# main.net
KiCad netlist of a schematic drawn in Altium Designer
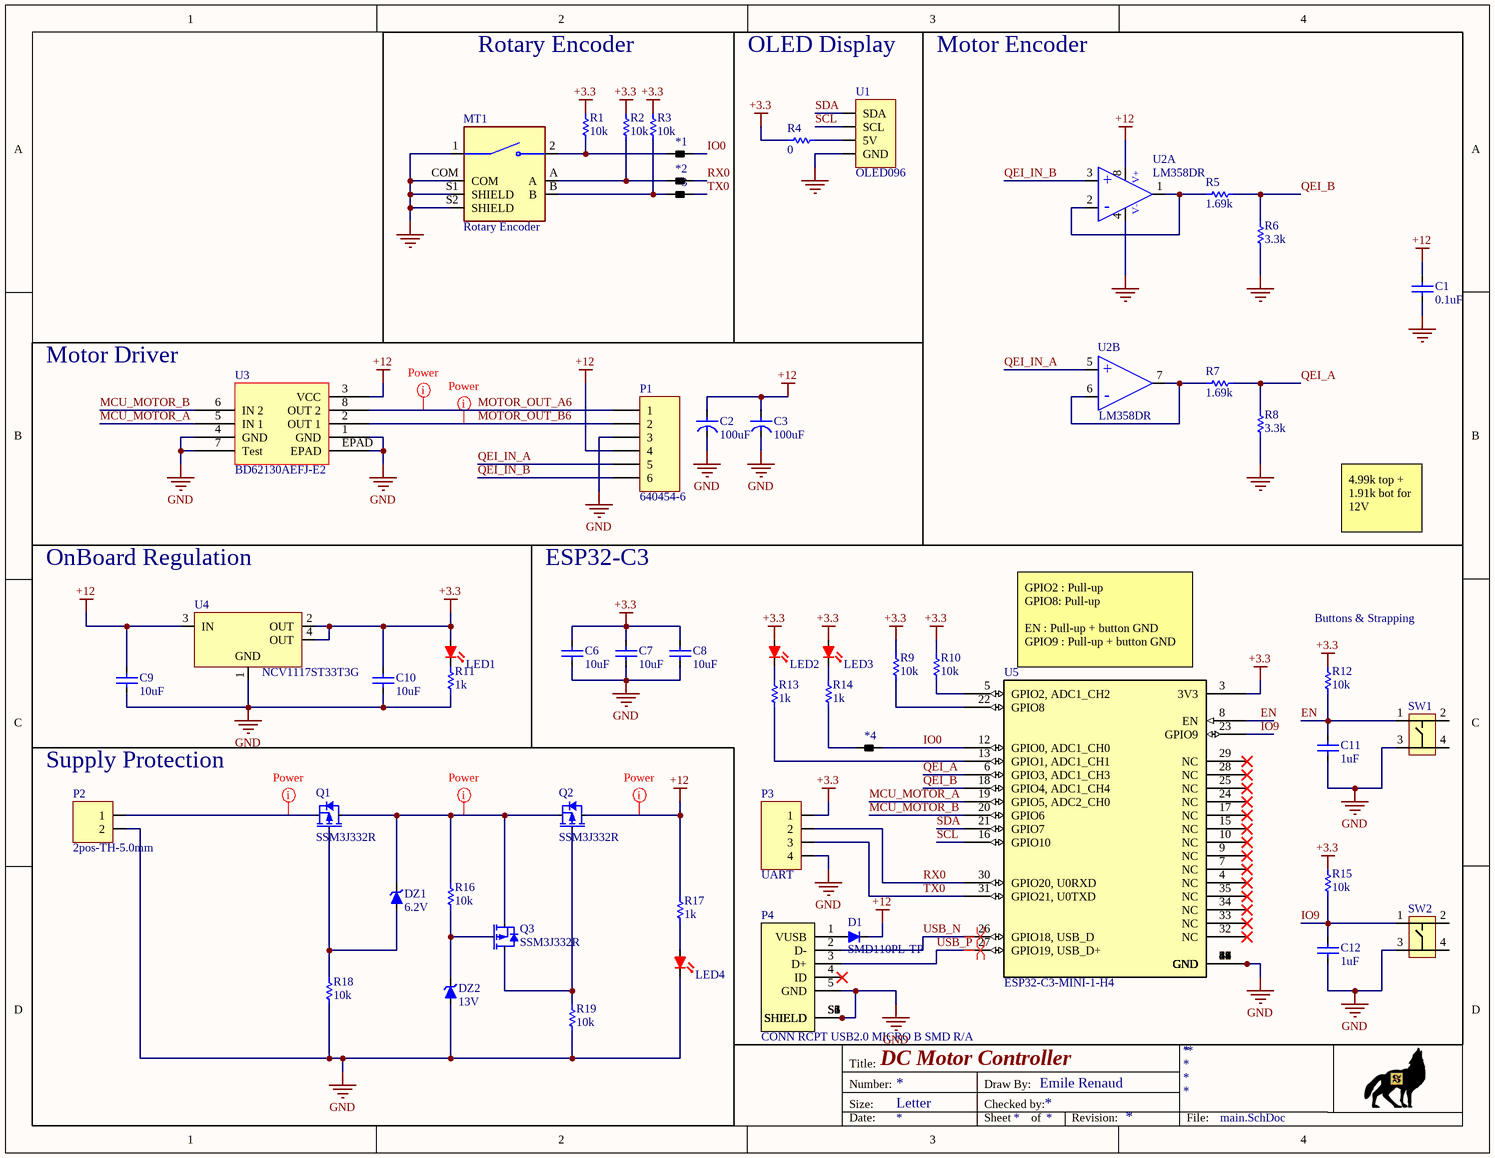
[diagram p0: main.SchDoc]

(export (version "E")
  (design (tool "Eeschema 10.0.6"))
  (components
    (comp (ref "*1")
      (value "NetTie_0603_Short")
      (footprint "NetTie-0603-short")
      (libsource (lib "JumpersAndHoles") (part "NetTie_0603_Short"))
    )
    (comp (ref "*2")
      (value "NetTie_0603_Short")
      (footprint "NetTie-0603-short")
      (libsource (lib "JumpersAndHoles") (part "NetTie_0603_Short"))
    )
    (comp (ref "*3")
      (value "NetTie_0603_Short")
      (footprint "NetTie-0603-short")
      (libsource (lib "JumpersAndHoles") (part "NetTie_0603_Short"))
    )
    (comp (ref "*4")
      (value "NetTie_0603_Short")
      (footprint "NetTie-0603-short")
      (libsource (lib "JumpersAndHoles") (part "NetTie_0603_Short"))
    )
    (comp (ref "C1")
      (value "0.1uF")
      (footprint "CAPACITOR-0603")
      (description "Capacitor-0603-0.1uF-50V-X7R")
      (libsource (lib "Capacitors") (part "Capacitor-0603-0.1uF-50V-X7R"))
    )
    (comp (ref "C2")
      (value "100uF")
      (footprint "CAPACITOR-Aluminium-5x11mm-2mmPitch")
      (description "CAP ALUM 100UF 20% 25V RADIAL")
      (libsource (lib "Capacitors-Electrolytic") (part "Capacitor-100uF-25V"))
    )
    (comp (ref "C3")
      (value "100uF")
      (footprint "CAPACITOR-Aluminium-5x11mm-2mmPitch")
      (description "CAP ALUM 100UF 20% 25V RADIAL")
      (libsource (lib "Capacitors-Electrolytic") (part "Capacitor-100uF-25V"))
    )
    (comp (ref "C6")
      (value "10uF")
      (footprint "CAPACITOR-0805")
      (description "Capacitor-0805-10uF-35V-X5R")
      (libsource (lib "Capacitors") (part "Capacitor-0805-10uF-35V-X5R"))
    )
    (comp (ref "C7")
      (value "10uF")
      (footprint "CAPACITOR-0805")
      (description "Capacitor-0805-10uF-35V-X5R")
      (libsource (lib "Capacitors") (part "Capacitor-0805-10uF-35V-X5R"))
    )
    (comp (ref "C8")
      (value "10uF")
      (footprint "CAPACITOR-0805")
      (description "Capacitor-0805-10uF-35V-X5R")
      (libsource (lib "Capacitors") (part "Capacitor-0805-10uF-35V-X5R"))
    )
    (comp (ref "C9")
      (value "10uF")
      (footprint "CAPACITOR-0805")
      (description "Capacitor-0805-10uF-35V-X5R")
      (libsource (lib "Capacitors") (part "Capacitor-0805-10uF-35V-X5R"))
    )
    (comp (ref "C10")
      (value "10uF")
      (footprint "CAPACITOR-0805")
      (description "Capacitor-0805-10uF-35V-X5R")
      (libsource (lib "Capacitors") (part "Capacitor-0805-10uF-35V-X5R"))
    )
    (comp (ref "C11")
      (value "1uF")
      (footprint "CAPACITOR-0603")
      (description "Capacitor-0603-1uF-25V-X5R")
      (libsource (lib "Capacitors") (part "Capacitor-0603-1uF-25V-X5R"))
    )
    (comp (ref "C12")
      (value "1uF")
      (footprint "CAPACITOR-0603")
      (description "Capacitor-0603-1uF-25V-X5R")
      (libsource (lib "Capacitors") (part "Capacitor-0603-1uF-25V-X5R"))
    )
    (comp (ref "D1")
      (value "SMD110PL-TP")
      (footprint "SOD-123F")
      (description "DIODE SCHOTTKY 100V 1A SOD123FL")
      (libsource (lib "diodes") (part "SMD110PL-TP"))
    )
    (comp (ref "DZ1")
      (value "BZT52C6V2-TP")
      (footprint "SOD-123")
      (description "Zener Diode 6.2 V 200 mW ±6% Surface Mount SOD-123")
      (fields (field (name "VOLT") "6.2V"))
      (libsource (lib "diodes-zener") (part "BZT52C6V2-TP"))
    )
    (comp (ref "DZ2")
      (value "BZT52C13-TP")
      (footprint "SOD-123")
      (description "Zener Diode 13 V 200 mW ±6% Surface Mount SOD-123")
      (fields (field (name "VOLT") "13V"))
      (libsource (lib "diodes-zener") (part "BZT52C13-TP"))
    )
    (comp (ref "LED1")
      (value "B1911USD-20D000114U1930")
      (footprint "LED-0603-2PIN")
      (description "LED RED CLEAR 1608 SMD")
      (libsource (lib "LEDs") (part "B1911USD-20D000114U1930"))
    )
    (comp (ref "LED2")
      (value "B1911USD-20D000114U1930")
      (footprint "LED-0603-2PIN")
      (description "LED RED CLEAR 1608 SMD")
      (libsource (lib "LEDs") (part "B1911USD-20D000114U1930"))
    )
    (comp (ref "LED3")
      (value "B1911USD-20D000114U1930")
      (footprint "LED-0603-2PIN")
      (description "LED RED CLEAR 1608 SMD")
      (libsource (lib "LEDs") (part "B1911USD-20D000114U1930"))
    )
    (comp (ref "LED4")
      (value "B1911USD-20D000114U1930")
      (footprint "LED-0603-2PIN")
      (description "LED RED CLEAR 1608 SMD")
      (libsource (lib "LEDs") (part "B1911USD-20D000114U1930"))
    )
    (comp (ref "MT1")
      (value "Rotary Encoder")
      (footprint "PCB_Footprints:XDCR_PEC11R-4215F-S0024")
      (description "Incremental Encoder, 12 Mm, Contact Rating 10 Ma - 5 Vdc")
      (fields (field (name "MP") "PEC11R-4215F-S0024"))
      (libsource (lib "Encoder") (part "PEC11R-4215F-S0024"))
    )
    (comp (ref "P1")
      (value "640454-6")
      (footprint "640454-6")
      (description "CONN HEADER VERT 6POS .100 TIN")
      (fields (field (name "MANUFACTURER") "TE Connectivity AMP Connectors"))
      (libsource (lib "header") (part "640454-6"))
    )
    (comp (ref "P2")
      (value "2pos-TH-5.0mm")
      (footprint "Weco 2")
      (description "2pos-TH-5.0mm Screw Terminal")
      (libsource (lib "ScrewTerminal") (part "2pos-TH-5.0mm"))
    )
    (comp (ref "P3")
      (value "UART")
      (footprint "HDR1X4")
      (description "4pos TH 2.54mm Header")
      (libsource (lib "header") (part "4pos-TH-2.54mm"))
    )
    (comp (ref "P4")
      (value "CONN RCPT USB2.0 MICRO B SMD R/A")
      (footprint "FCI_10118193-0001LF")
      (description "USB - micro B USB 2.0 Receptacle Connector 5 Position Surface Mount, Right Angle; Through Hole")
      (libsource (lib "PC-connector") (part "USB-Micro"))
    )
    (comp (ref "Q1")
      (value "SSM3J332R")
      (footprint "SOT-23-3")
      (description "P-Channel 30 V 6A (Ta) 1W (Ta) Surface Mount SOT-23F")
      (libsource (lib "FET-P-Small") (part "SSM3J332R"))
    )
    (comp (ref "Q2")
      (value "SSM3J332R")
      (footprint "SOT-23-3")
      (description "P-Channel 30 V 6A (Ta) 1W (Ta) Surface Mount SOT-23F")
      (libsource (lib "FET-P-Small") (part "SSM3J332R"))
    )
    (comp (ref "Q3")
      (value "SSM3J332R")
      (footprint "SOT-23-3")
      (description "P-Channel 30 V 6A (Ta) 1W (Ta) Surface Mount SOT-23F")
      (libsource (lib "FET-P-Small") (part "SSM3J332R"))
    )
    (comp (ref "R1")
      (value "10k")
      (footprint "Resistor-0603")
      (description "Resistor0603-10k")
      (fields (field (name "Comment") "SMT resistor"))
      (libsource (lib "Resistors") (part "Resistor0603-10k"))
    )
    (comp (ref "R2")
      (value "10k")
      (footprint "Resistor-0603")
      (description "Resistor0603-10k")
      (fields (field (name "Comment") "SMT resistor"))
      (libsource (lib "Resistors") (part "Resistor0603-10k"))
    )
    (comp (ref "R3")
      (value "10k")
      (footprint "Resistor-0603")
      (description "Resistor0603-10k")
      (fields (field (name "Comment") "SMT resistor"))
      (libsource (lib "Resistors") (part "Resistor0603-10k"))
    )
    (comp (ref "R4")
      (value "0")
      (footprint "Resistor-0603")
      (description "Resistor0603-0.0")
      (fields (field (name "Comment") "SMT resistor"))
      (libsource (lib "Resistors") (part "Resistor0603-0.0"))
    )
    (comp (ref "R5")
      (value "1.69k")
      (footprint "Resistor-0603")
      (description "Resistor0603-1.69k")
      (fields (field (name "Comment") "SMT resistor"))
      (libsource (lib "Resistors") (part "Resistor0603-1.69k"))
    )
    (comp (ref "R6")
      (value "3.3k")
      (footprint "Resistor-0603")
      (description "Resistor0603-3.3k")
      (fields (field (name "Comment") "SMT resistor"))
      (libsource (lib "Resistors") (part "Resistor0603-3.3k"))
    )
    (comp (ref "R7")
      (value "1.69k")
      (footprint "Resistor-0603")
      (description "Resistor0603-1.69k")
      (fields (field (name "Comment") "SMT resistor"))
      (libsource (lib "Resistors") (part "Resistor0603-1.69k"))
    )
    (comp (ref "R8")
      (value "3.3k")
      (footprint "Resistor-0603")
      (description "Resistor0603-3.3k")
      (fields (field (name "Comment") "SMT resistor"))
      (libsource (lib "Resistors") (part "Resistor0603-3.3k"))
    )
    (comp (ref "R9")
      (value "10k")
      (footprint "Resistor-0603")
      (description "Resistor0603-10k")
      (fields (field (name "Comment") "SMT resistor"))
      (libsource (lib "Resistors") (part "Resistor0603-10k"))
    )
    (comp (ref "R10")
      (value "10k")
      (footprint "Resistor-0603")
      (description "Resistor0603-10k")
      (fields (field (name "Comment") "SMT resistor"))
      (libsource (lib "Resistors") (part "Resistor0603-10k"))
    )
    (comp (ref "R11")
      (value "1k")
      (footprint "Resistor-0603")
      (description "Resistor0603-1k")
      (fields (field (name "Comment") "SMT resistor"))
      (libsource (lib "Resistors") (part "Resistor0603-1k"))
    )
    (comp (ref "R12")
      (value "10k")
      (footprint "Resistor-0603")
      (description "Resistor0603-10k")
      (fields (field (name "Comment") "SMT resistor"))
      (libsource (lib "Resistors") (part "Resistor0603-10k"))
    )
    (comp (ref "R13")
      (value "1k")
      (footprint "Resistor-0603")
      (description "Resistor0603-1k")
      (fields (field (name "Comment") "SMT resistor"))
      (libsource (lib "Resistors") (part "Resistor0603-1k"))
    )
    (comp (ref "R14")
      (value "1k")
      (footprint "Resistor-0603")
      (description "Resistor0603-1k")
      (fields (field (name "Comment") "SMT resistor"))
      (libsource (lib "Resistors") (part "Resistor0603-1k"))
    )
    (comp (ref "R15")
      (value "10k")
      (footprint "Resistor-0603")
      (description "Resistor0603-10k")
      (fields (field (name "Comment") "SMT resistor"))
      (libsource (lib "Resistors") (part "Resistor0603-10k"))
    )
    (comp (ref "R16")
      (value "10k")
      (footprint "Resistor-0603")
      (description "Resistor0603-10k")
      (fields (field (name "Comment") "SMT resistor"))
      (libsource (lib "Resistors") (part "Resistor0603-10k"))
    )
    (comp (ref "R17")
      (value "1k")
      (footprint "Resistor-0603")
      (description "Resistor0603-1k")
      (fields (field (name "Comment") "SMT resistor"))
      (libsource (lib "Resistors") (part "Resistor0603-1k"))
    )
    (comp (ref "R18")
      (value "10k")
      (footprint "Resistor-0603")
      (description "Resistor0603-10k")
      (fields (field (name "Comment") "SMT resistor"))
      (libsource (lib "Resistors") (part "Resistor0603-10k"))
    )
    (comp (ref "R19")
      (value "10k")
      (footprint "Resistor-0603")
      (description "Resistor0603-10k")
      (fields (field (name "Comment") "SMT resistor"))
      (libsource (lib "Resistors") (part "Resistor0603-10k"))
    )
    (comp (ref "SW1")
      (value "PTS815 SJM 250 SMTR LFS")
      (footprint "SW4_PTS815 SJM 250 SMTR LFS_CNK")
      (description "TACT 4.2 X 3.2, 2.5 MM H, 180GF,")
      (libsource (lib "THTPushButtonSwitches") (part "PTS815 SJM 250 SMTR LFS"))
    )
    (comp (ref "SW2")
      (value "PTS815 SJM 250 SMTR LFS")
      (footprint "SW4_PTS815 SJM 250 SMTR LFS_CNK")
      (description "TACT 4.2 X 3.2, 2.5 MM H, 180GF,")
      (libsource (lib "THTPushButtonSwitches") (part "PTS815 SJM 250 SMTR LFS"))
    )
    (comp (ref "U1")
      (value "OLED096")
      (footprint "OLED096")
      (description "OLED Display I2C 0.96in")
      (libsource (lib "LCD") (part "OLED096"))
    )
    (comp (ref "U2")
      (value "LM358DR")
      (footprint "SOIC-8")
      (description "IC OPAMP GP 2 CIRCUIT 8SOIC")
      (libsource (lib "OperationalAmplifiers") (part "LM358DR"))
    )
    (comp (ref "U3")
      (value "BD62130AEFJ-E2")
      (footprint "P-HSOP8")
      (description "1 CHANNEL H BRIDGE Motor. 28V, 3A")
      (libsource (lib "MotorDrivers") (part "BD62130AEFJ-E2"))
    )
    (comp (ref "U4")
      (value "NCV1117ST33T3G")
      (footprint "SOT-223-3/TO-261-3S")
      (description "IC REG LINEAR 3.3V 1A SOT223")
      (libsource (lib "PMIC-VoltageRegulators-LinearRegulators") (part "NCV1117ST33T3G"))
    )
    (comp (ref "U5")
      (value "ESP32-C3-MINI-1-H4")
      (footprint "ESP32-C3-MINI-1_EXP")
      (fields
        (field (name "MANUFACTURER_PART_NUMBER") "ESP32-C3-MINI-1-N4")
        (field (name "COPYRIGHT") "Copyright (C) 2023 Ultra Librarian. All rights reserved.")
      )
      (libsource (lib "Microcontrollers") (part "ESP32-C3-MINI-1-N4"))
    )
  )
  (nets
    (net (code "1") (name "+3.3") (class "Default")
      (node (ref "C10") (pin "2") (pinfunction "2_2") (pintype "passive"))
      (node (ref "C6") (pin "2") (pinfunction "2_2") (pintype "passive"))
      (node (ref "C7") (pin "2") (pinfunction "2_2") (pintype "passive"))
      (node (ref "C8") (pin "2") (pinfunction "2_2") (pintype "passive"))
      (node (ref "LED1") (pin "2") (pinfunction "R_2") (pintype "passive"))
      (node (ref "LED2") (pin "2") (pinfunction "R_2") (pintype "passive"))
      (node (ref "LED3") (pin "2") (pinfunction "R_2") (pintype "passive"))
      (node (ref "P3") (pin "1") (pinfunction "1_1") (pintype "passive"))
      (node (ref "R1") (pin "1") (pinfunction "1_1") (pintype "passive"))
      (node (ref "R10") (pin "1") (pinfunction "1_1") (pintype "passive"))
      (node (ref "R12") (pin "2") (pinfunction "2_2") (pintype "passive"))
      (node (ref "R15") (pin "2") (pinfunction "2_2") (pintype "passive"))
      (node (ref "R2") (pin "1") (pinfunction "1_1") (pintype "passive"))
      (node (ref "R3") (pin "1") (pinfunction "1_1") (pintype "passive"))
      (node (ref "R4") (pin "1") (pinfunction "1_1") (pintype "passive"))
      (node (ref "R9") (pin "1") (pinfunction "1_1") (pintype "passive"))
      (node (ref "U4") (pin "2") (pinfunction "OUT_2") (pintype "passive"))
      (node (ref "U4") (pin "4") (pinfunction "OUT_4") (pintype "passive"))
      (node (ref "U5") (pin "3") (pinfunction "3V3_3") (pintype "power_in"))
    )
    (net (code "2") (name "+12") (class "Default")
      (node (ref "C1") (pin "2") (pinfunction "2_2") (pintype "passive"))
      (node (ref "C2") (pin "1") (pinfunction "1_1") (pintype "passive"))
      (node (ref "C3") (pin "1") (pinfunction "1_1") (pintype "passive"))
      (node (ref "C9") (pin "2") (pinfunction "2_2") (pintype "passive"))
      (node (ref "D1") (pin "2") (pinfunction "K_2") (pintype "passive"))
      (node (ref "P1") (pin "4") (pinfunction "4_4") (pintype "passive"))
      (node (ref "Q2") (pin "3") (pinfunction "D_3") (pintype "passive"))
      (node (ref "R17") (pin "2") (pinfunction "2_2") (pintype "passive"))
      (node (ref "U2") (pin "8") (pinfunction "VS+_8") (pintype "passive"))
      (node (ref "U3") (pin "3") (pinfunction "VCC_3") (pintype "passive"))
      (node (ref "U4") (pin "3") (pinfunction "IN_3") (pintype "passive"))
    )
    (net (code "3") (name "/EN") (class "Default")
      (node (ref "C11") (pin "2") (pinfunction "2_2") (pintype "passive"))
      (node (ref "R12") (pin "1") (pinfunction "1_1") (pintype "passive"))
      (node (ref "SW1") (pin "1") (pinfunction "1_1") (pintype "passive"))
      (node (ref "U5") (pin "8") (pinfunction "EN_8") (pintype "input"))
    )
    (net (code "4") (name "/IO0") (class "Default")
      (node (ref "*1") (pin "1") (pinfunction "1_1") (pintype "passive"))
      (node (ref "*4") (pin "1") (pinfunction "1_1") (pintype "passive"))
      (node (ref "U5") (pin "12") (pinfunction "GPIO0,_ADC1_CH0_12") (pintype "bidirectional"))
    )
    (net (code "5") (name "/IO9") (class "Default")
      (node (ref "C12") (pin "2") (pinfunction "2_2") (pintype "passive"))
      (node (ref "R15") (pin "1") (pinfunction "1_1") (pintype "passive"))
      (node (ref "SW2") (pin "1") (pinfunction "1_1") (pintype "passive"))
      (node (ref "U5") (pin "23") (pinfunction "GPIO9_23") (pintype "bidirectional"))
    )
    (net (code "6") (name "/MCU_MOTOR_A") (class "Default")
      (node (ref "U3") (pin "5") (pinfunction "IN_1_5") (pintype "passive"))
      (node (ref "U5") (pin "19") (pinfunction "GPIO5,_ADC2_CH0_19") (pintype "bidirectional"))
    )
    (net (code "7") (name "/MCU_MOTOR_B") (class "Default")
      (node (ref "U3") (pin "6") (pinfunction "IN_2_6") (pintype "passive"))
      (node (ref "U5") (pin "20") (pinfunction "GPIO6_20") (pintype "bidirectional"))
    )
    (net (code "8") (name "/MOTOR_OUT_A6") (class "Default")
      (node (ref "P1") (pin "1") (pinfunction "1_1") (pintype "passive"))
      (node (ref "U3") (pin "8") (pinfunction "OUT_2_8") (pintype "passive"))
    )
    (net (code "9") (name "/MOTOR_OUT_B6") (class "Default")
      (node (ref "P1") (pin "2") (pinfunction "2_2") (pintype "passive"))
      (node (ref "U3") (pin "2") (pinfunction "OUT_1_2") (pintype "passive"))
    )
    (net (code "10") (name "/QEI_A") (class "Default")
      (node (ref "R7") (pin "2") (pinfunction "2_2") (pintype "passive"))
      (node (ref "R8") (pin "2") (pinfunction "2_2") (pintype "passive"))
      (node (ref "U5") (pin "6") (pinfunction "GPIO3,_ADC1_CH3_6") (pintype "bidirectional"))
    )
    (net (code "11") (name "/QEI_B") (class "Default")
      (node (ref "R5") (pin "2") (pinfunction "2_2") (pintype "passive"))
      (node (ref "R6") (pin "2") (pinfunction "2_2") (pintype "passive"))
      (node (ref "U5") (pin "18") (pinfunction "GPIO4,_ADC1_CH4_18") (pintype "bidirectional"))
    )
    (net (code "12") (name "/QEI_IN_A") (class "Default")
      (node (ref "P1") (pin "5") (pinfunction "5_5") (pintype "passive"))
      (node (ref "U2") (pin "5") (pinfunction "IN2+_5") (pintype "passive"))
    )
    (net (code "13") (name "/QEI_IN_B") (class "Default")
      (node (ref "P1") (pin "6") (pinfunction "6_6") (pintype "passive"))
      (node (ref "U2") (pin "3") (pinfunction "IN1+_3") (pintype "passive"))
    )
    (net (code "14") (name "/RX0") (class "Default")
      (node (ref "*2") (pin "1") (pinfunction "1_1") (pintype "passive"))
      (node (ref "P3") (pin "2") (pinfunction "2_2") (pintype "passive"))
      (node (ref "U5") (pin "30") (pinfunction "GPIO20,_U0RXD_30") (pintype "bidirectional"))
    )
    (net (code "15") (name "/SCL") (class "Default")
      (node (ref "U1") (pin "3") (pinfunction "SCL_3") (pintype "passive"))
      (node (ref "U5") (pin "16") (pinfunction "GPIO10_16") (pintype "bidirectional"))
    )
    (net (code "16") (name "/SDA") (class "Default")
      (node (ref "U1") (pin "4") (pinfunction "SDA_4") (pintype "passive"))
      (node (ref "U5") (pin "21") (pinfunction "GPIO7_21") (pintype "bidirectional"))
    )
    (net (code "17") (name "/TX0") (class "Default")
      (node (ref "*3") (pin "1") (pinfunction "1_1") (pintype "passive"))
      (node (ref "P3") (pin "3") (pinfunction "3_3") (pintype "passive"))
      (node (ref "U5") (pin "31") (pinfunction "GPIO21,_U0TXD_31") (pintype "bidirectional"))
    )
    (net (code "18") (name "/USB_N") (class "Default")
      (node (ref "P4") (pin "2") (pinfunction "D-_2") (pintype "passive"))
      (node (ref "U5") (pin "26") (pinfunction "GPIO18,_USB_D_26") (pintype "bidirectional"))
    )
    (net (code "19") (name "/USB_P") (class "Default")
      (node (ref "P4") (pin "3") (pinfunction "D+_3") (pintype "passive"))
      (node (ref "U5") (pin "27") (pinfunction "GPIO19,_USB_D+_27") (pintype "bidirectional"))
    )
    (net (code "20") (name "GND") (class "Default")
      (node (ref "C1") (pin "1") (pinfunction "1_1") (pintype "passive"))
      (node (ref "C10") (pin "1") (pinfunction "1_1") (pintype "passive"))
      (node (ref "C11") (pin "1") (pinfunction "1_1") (pintype "passive"))
      (node (ref "C12") (pin "1") (pinfunction "1_1") (pintype "passive"))
      (node (ref "C2") (pin "2") (pinfunction "2_2") (pintype "passive"))
      (node (ref "C3") (pin "2") (pinfunction "2_2") (pintype "passive"))
      (node (ref "C6") (pin "1") (pinfunction "1_1") (pintype "passive"))
      (node (ref "C7") (pin "1") (pinfunction "1_1") (pintype "passive"))
      (node (ref "C8") (pin "1") (pinfunction "1_1") (pintype "passive"))
      (node (ref "C9") (pin "1") (pinfunction "1_1") (pintype "passive"))
      (node (ref "DZ2") (pin "1") (pinfunction "A_1") (pintype "passive"))
      (node (ref "LED4") (pin "1") (pinfunction "K_1") (pintype "passive"))
      (node (ref "MT1") (pin "1") (pinfunction "1_1") (pintype "passive"))
      (node (ref "MT1") (pin "COM") (pinfunction "COM_COM") (pintype "passive"))
      (node (ref "MT1") (pin "S1") (pinfunction "SHIELD_S1") (pintype "passive"))
      (node (ref "MT1") (pin "S2") (pinfunction "SHIELD_S2") (pintype "passive"))
      (node (ref "P1") (pin "3") (pinfunction "3_3") (pintype "passive"))
      (node (ref "P2") (pin "2") (pinfunction "2_2") (pintype "passive"))
      (node (ref "P3") (pin "4") (pinfunction "4_4") (pintype "passive"))
      (node (ref "P4") (pin "5") (pinfunction "GND_5") (pintype "passive"))
      (node (ref "P4") (pin "S1") (pinfunction "SHIELD_S1") (pintype "passive"))
      (node (ref "P4") (pin "S2") (pinfunction "SHIELD_S2") (pintype "passive"))
      (node (ref "P4") (pin "S3") (pinfunction "SHIELD_S3") (pintype "passive"))
      (node (ref "P4") (pin "S4") (pinfunction "SHIELD_S4") (pintype "passive"))
      (node (ref "P4") (pin "S5") (pinfunction "SHIELD_S5") (pintype "passive"))
      (node (ref "P4") (pin "S6") (pinfunction "SHIELD_S6") (pintype "passive"))
      (node (ref "R11") (pin "1") (pinfunction "1_1") (pintype "passive"))
      (node (ref "R18") (pin "1") (pinfunction "1_1") (pintype "passive"))
      (node (ref "R19") (pin "1") (pinfunction "1_1") (pintype "passive"))
      (node (ref "R6") (pin "1") (pinfunction "1_1") (pintype "passive"))
      (node (ref "R8") (pin "1") (pinfunction "1_1") (pintype "passive"))
      (node (ref "SW1") (pin "3") (pinfunction "3_3") (pintype "passive"))
      (node (ref "SW2") (pin "3") (pinfunction "3_3") (pintype "passive"))
      (node (ref "U1") (pin "1") (pinfunction "GND_1") (pintype "passive"))
      (node (ref "U2") (pin "4") (pinfunction "VS-_4") (pintype "passive"))
      (node (ref "U3") (pin "1") (pinfunction "GND_1") (pintype "passive"))
      (node (ref "U3") (pin "4") (pinfunction "GND_4") (pintype "passive"))
      (node (ref "U3") (pin "7") (pinfunction "Test_7") (pintype "passive"))
      (node (ref "U3") (pin "EPAD") (pinfunction "EPAD_EPAD") (pintype "passive"))
      (node (ref "U4") (pin "1") (pinfunction "GND_1") (pintype "passive"))
      (node (ref "U5") (pin "1") (pinfunction "GND_1") (pintype "passive"))
      (node (ref "U5") (pin "11") (pinfunction "GND_11") (pintype "passive"))
      (node (ref "U5") (pin "14") (pinfunction "GND_14") (pintype "passive"))
      (node (ref "U5") (pin "2") (pinfunction "GND_2") (pintype "passive"))
      (node (ref "U5") (pin "36") (pinfunction "GND_36") (pintype "passive"))
      (node (ref "U5") (pin "37") (pinfunction "GND_37") (pintype "passive"))
      (node (ref "U5") (pin "38") (pinfunction "GND_38") (pintype "passive"))
      (node (ref "U5") (pin "39") (pinfunction "GND_39") (pintype "passive"))
      (node (ref "U5") (pin "40") (pinfunction "GND_40") (pintype "passive"))
      (node (ref "U5") (pin "41") (pinfunction "GND_41") (pintype "passive"))
      (node (ref "U5") (pin "42") (pinfunction "GND_42") (pintype "passive"))
      (node (ref "U5") (pin "43") (pinfunction "GND_43") (pintype "passive"))
      (node (ref "U5") (pin "44") (pinfunction "GND_44") (pintype "passive"))
      (node (ref "U5") (pin "45") (pinfunction "GND_45") (pintype "passive"))
      (node (ref "U5") (pin "46") (pinfunction "GND_46") (pintype "passive"))
      (node (ref "U5") (pin "47") (pinfunction "GND_47") (pintype "passive"))
      (node (ref "U5") (pin "48") (pinfunction "GND_48") (pintype "passive"))
      (node (ref "U5") (pin "49") (pinfunction "GND_49") (pintype "passive"))
      (node (ref "U5") (pin "50") (pinfunction "GND_50") (pintype "passive"))
      (node (ref "U5") (pin "51") (pinfunction "GND_51") (pintype "passive"))
      (node (ref "U5") (pin "52") (pinfunction "GND_52") (pintype "passive"))
      (node (ref "U5") (pin "53") (pinfunction "GND_53") (pintype "passive"))
      (node (ref "U5") (pin "54") (pinfunction "GND_54") (pintype "passive"))
      (node (ref "U5") (pin "55") (pinfunction "GND_55") (pintype "passive"))
      (node (ref "U5") (pin "56") (pinfunction "GND_56") (pintype "passive"))
      (node (ref "U5") (pin "57") (pinfunction "GND_57") (pintype "passive"))
      (node (ref "U5") (pin "58") (pinfunction "GND_58") (pintype "passive"))
      (node (ref "U5") (pin "59") (pinfunction "GND_59") (pintype "passive"))
      (node (ref "U5") (pin "60") (pinfunction "GND_60") (pintype "passive"))
      (node (ref "U5") (pin "61") (pinfunction "GND_61") (pintype "passive"))
    )
    (net (code "21") (name "Net-(*1-Pad2)") (class "Default")
      (node (ref "*1") (pin "2") (pinfunction "2_2") (pintype "passive"))
      (node (ref "MT1") (pin "2") (pinfunction "2_2") (pintype "passive"))
      (node (ref "R1") (pin "2") (pinfunction "2_2") (pintype "passive"))
    )
    (net (code "22") (name "Net-(*2-Pad2)") (class "Default")
      (node (ref "*2") (pin "2") (pinfunction "2_2") (pintype "passive"))
      (node (ref "MT1") (pin "A") (pinfunction "A_A") (pintype "passive"))
      (node (ref "R2") (pin "2") (pinfunction "2_2") (pintype "passive"))
    )
    (net (code "23") (name "Net-(*3-Pad2)") (class "Default")
      (node (ref "*3") (pin "2") (pinfunction "2_2") (pintype "passive"))
      (node (ref "MT1") (pin "B") (pinfunction "B_B") (pintype "passive"))
      (node (ref "R3") (pin "2") (pinfunction "2_2") (pintype "passive"))
    )
    (net (code "24") (name "Net-(*4-Pad2)") (class "Default")
      (node (ref "*4") (pin "2") (pinfunction "2_2") (pintype "passive"))
      (node (ref "R14") (pin "1") (pinfunction "1_1") (pintype "passive"))
    )
    (net (code "25") (name "Net-(D1-A)") (class "Default")
      (node (ref "D1") (pin "1") (pinfunction "A_1") (pintype "passive"))
      (node (ref "P4") (pin "1") (pinfunction "VUSB_1") (pintype "passive"))
    )
    (net (code "26") (name "Net-(DZ1-A)") (class "Default")
      (node (ref "DZ1") (pin "1") (pinfunction "A_1") (pintype "passive"))
      (node (ref "Q1") (pin "1") (pinfunction "G_1") (pintype "passive"))
      (node (ref "R18") (pin "2") (pinfunction "2_2") (pintype "passive"))
    )
    (net (code "27") (name "Net-(DZ1-K)") (class "Default")
      (node (ref "DZ1") (pin "2") (pinfunction "K_2") (pintype "passive"))
      (node (ref "Q1") (pin "3") (pinfunction "D_3") (pintype "passive"))
      (node (ref "Q2") (pin "2") (pinfunction "S_2") (pintype "passive"))
      (node (ref "Q3") (pin "2") (pinfunction "S_2") (pintype "passive"))
      (node (ref "R16") (pin "2") (pinfunction "2_2") (pintype "passive"))
    )
    (net (code "28") (name "Net-(DZ2-K)") (class "Default")
      (node (ref "DZ2") (pin "2") (pinfunction "K_2") (pintype "passive"))
      (node (ref "Q3") (pin "1") (pinfunction "G_1") (pintype "passive"))
      (node (ref "R16") (pin "1") (pinfunction "1_1") (pintype "passive"))
    )
    (net (code "29") (name "Net-(LED1-K)") (class "Default")
      (node (ref "LED1") (pin "1") (pinfunction "K_1") (pintype "passive"))
      (node (ref "R11") (pin "2") (pinfunction "2_2") (pintype "passive"))
    )
    (net (code "30") (name "Net-(LED2-K)") (class "Default")
      (node (ref "LED2") (pin "1") (pinfunction "K_1") (pintype "passive"))
      (node (ref "R13") (pin "2") (pinfunction "2_2") (pintype "passive"))
    )
    (net (code "31") (name "Net-(LED3-K)") (class "Default")
      (node (ref "LED3") (pin "1") (pinfunction "K_1") (pintype "passive"))
      (node (ref "R14") (pin "2") (pinfunction "2_2") (pintype "passive"))
    )
    (net (code "32") (name "Net-(LED4-R)") (class "Default")
      (node (ref "LED4") (pin "2") (pinfunction "R_2") (pintype "passive"))
      (node (ref "R17") (pin "1") (pinfunction "1_1") (pintype "passive"))
    )
    (net (code "33") (name "Net-(Q1-S)") (class "Default")
      (node (ref "P2") (pin "1") (pinfunction "1_1") (pintype "passive"))
      (node (ref "Q1") (pin "2") (pinfunction "S_2") (pintype "passive"))
    )
    (net (code "34") (name "Net-(Q2-G)") (class "Default")
      (node (ref "Q2") (pin "1") (pinfunction "G_1") (pintype "passive"))
      (node (ref "Q3") (pin "3") (pinfunction "D_3") (pintype "passive"))
      (node (ref "R19") (pin "2") (pinfunction "2_2") (pintype "passive"))
    )
    (net (code "35") (name "Net-(U1-5V)") (class "Default")
      (node (ref "R4") (pin "2") (pinfunction "2_2") (pintype "passive"))
      (node (ref "U1") (pin "2") (pinfunction "5V_2") (pintype "passive"))
    )
    (net (code "36") (name "Net-(U2A-IN1-)") (class "Default")
      (node (ref "R5") (pin "1") (pinfunction "1_1") (pintype "passive"))
      (node (ref "U2") (pin "1") (pinfunction "OUT1_1") (pintype "passive"))
      (node (ref "U2") (pin "2") (pinfunction "IN1-_2") (pintype "passive"))
    )
    (net (code "37") (name "Net-(U2B-IN2-)") (class "Default")
      (node (ref "R7") (pin "1") (pinfunction "1_1") (pintype "passive"))
      (node (ref "U2") (pin "6") (pinfunction "IN2-_6") (pintype "passive"))
      (node (ref "U2") (pin "7") (pinfunction "OUT_7") (pintype "passive"))
    )
    (net (code "38") (name "Net-(U5-GPIO1,_ADC1_CH1)") (class "Default")
      (node (ref "R13") (pin "1") (pinfunction "1_1") (pintype "passive"))
      (node (ref "U5") (pin "13") (pinfunction "GPIO1,_ADC1_CH1_13") (pintype "bidirectional"))
    )
    (net (code "39") (name "Net-(U5-GPIO2,_ADC1_CH2)") (class "Default")
      (node (ref "R10") (pin "2") (pinfunction "2_2") (pintype "passive"))
      (node (ref "U5") (pin "5") (pinfunction "GPIO2,_ADC1_CH2_5") (pintype "bidirectional"))
    )
    (net (code "40") (name "Net-(U5-GPIO8)") (class "Default")
      (node (ref "R9") (pin "2") (pinfunction "2_2") (pintype "passive"))
      (node (ref "U5") (pin "22") (pinfunction "GPIO8_22") (pintype "bidirectional"))
    )
    (net (code "41") (name "unconnected-(P4-ID-Pad4)") (class "Default")
      (node (ref "P4") (pin "4") (pinfunction "ID_4") (pintype "passive+no_connect"))
    )
    (net (code "42") (name "unconnected-(SW1-Pad2)") (class "Default")
      (node (ref "SW1") (pin "2") (pinfunction "2_2") (pintype "passive"))
    )
    (net (code "43") (name "unconnected-(SW1-Pad4)") (class "Default")
      (node (ref "SW1") (pin "4") (pinfunction "4_4") (pintype "passive"))
    )
    (net (code "44") (name "unconnected-(SW2-Pad2)") (class "Default")
      (node (ref "SW2") (pin "2") (pinfunction "2_2") (pintype "passive"))
    )
    (net (code "45") (name "unconnected-(SW2-Pad4)") (class "Default")
      (node (ref "SW2") (pin "4") (pinfunction "4_4") (pintype "passive"))
    )
    (net (code "46") (name "unconnected-(U5-NC-Pad4)") (class "Default")
      (node (ref "U5") (pin "4") (pinfunction "NC_4") (pintype "passive+no_connect"))
    )
    (net (code "47") (name "unconnected-(U5-NC-Pad7)") (class "Default")
      (node (ref "U5") (pin "7") (pinfunction "NC_7") (pintype "passive+no_connect"))
    )
    (net (code "48") (name "unconnected-(U5-NC-Pad9)") (class "Default")
      (node (ref "U5") (pin "9") (pinfunction "NC_9") (pintype "passive+no_connect"))
    )
    (net (code "49") (name "unconnected-(U5-NC-Pad10)") (class "Default")
      (node (ref "U5") (pin "10") (pinfunction "NC_10") (pintype "passive+no_connect"))
    )
    (net (code "50") (name "unconnected-(U5-NC-Pad15)") (class "Default")
      (node (ref "U5") (pin "15") (pinfunction "NC_15") (pintype "passive+no_connect"))
    )
    (net (code "51") (name "unconnected-(U5-NC-Pad17)") (class "Default")
      (node (ref "U5") (pin "17") (pinfunction "NC_17") (pintype "passive+no_connect"))
    )
    (net (code "52") (name "unconnected-(U5-NC-Pad24)") (class "Default")
      (node (ref "U5") (pin "24") (pinfunction "NC_24") (pintype "passive+no_connect"))
    )
    (net (code "53") (name "unconnected-(U5-NC-Pad25)") (class "Default")
      (node (ref "U5") (pin "25") (pinfunction "NC_25") (pintype "passive+no_connect"))
    )
    (net (code "54") (name "unconnected-(U5-NC-Pad28)") (class "Default")
      (node (ref "U5") (pin "28") (pinfunction "NC_28") (pintype "passive+no_connect"))
    )
    (net (code "55") (name "unconnected-(U5-NC-Pad29)") (class "Default")
      (node (ref "U5") (pin "29") (pinfunction "NC_29") (pintype "passive+no_connect"))
    )
    (net (code "56") (name "unconnected-(U5-NC-Pad32)") (class "Default")
      (node (ref "U5") (pin "32") (pinfunction "NC_32") (pintype "passive+no_connect"))
    )
    (net (code "57") (name "unconnected-(U5-NC-Pad33)") (class "Default")
      (node (ref "U5") (pin "33") (pinfunction "NC_33") (pintype "passive+no_connect"))
    )
    (net (code "58") (name "unconnected-(U5-NC-Pad34)") (class "Default")
      (node (ref "U5") (pin "34") (pinfunction "NC_34") (pintype "passive+no_connect"))
    )
    (net (code "59") (name "unconnected-(U5-NC-Pad35)") (class "Default")
      (node (ref "U5") (pin "35") (pinfunction "NC_35") (pintype "passive+no_connect"))
    )
  )
)
